# GPIO_Raspberry_b.net
KiCad netlist of a schematic drawn in Altium Designer
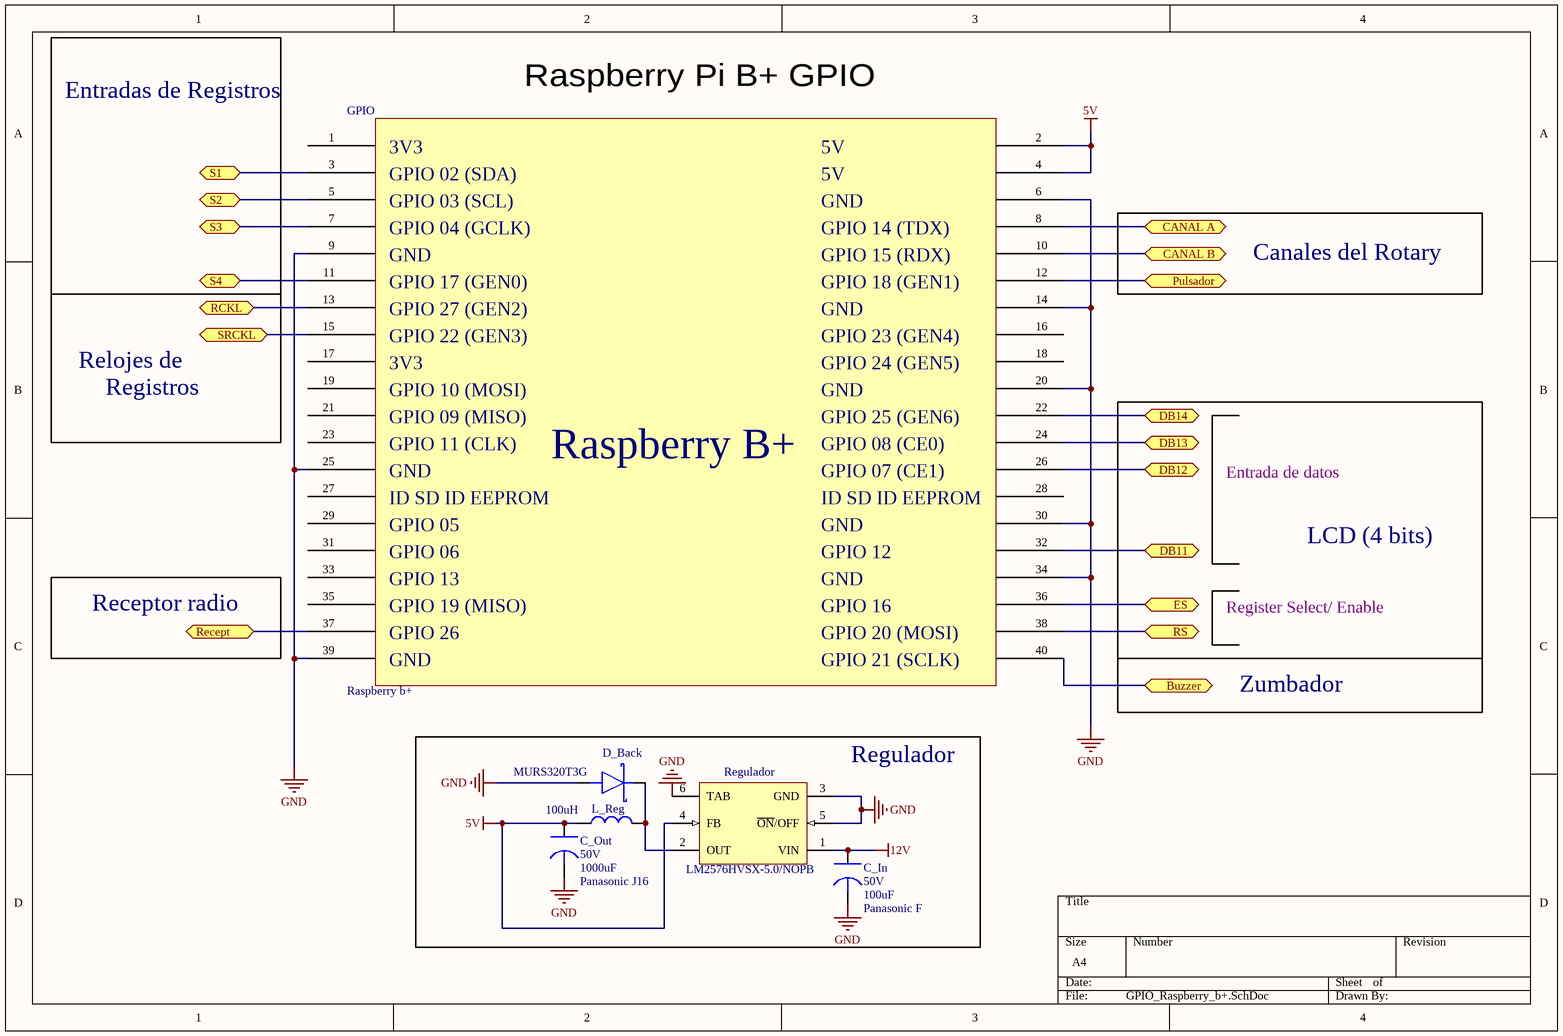
[diagram p0: GPIO_Raspberry_b+.SchDoc]

(export (version "E")
  (design (tool "Eeschema 10.0.6"))
  (components
    (comp (ref "C_In")
      (value "100uF")
      (footprint "Panasonic F Size")
      (description "Condensador Electrolítico SMD")
      (fields
        (field (name "PART NUMBER") "EMV-500ADA101MJA0G")
        (field (name "TOLERANCE") "20%")
        (field (name "VOLTAGE RATING") "50V")
        (field (name "PCB DECAL") "Panasonic F")
        (field (name "AUTHOR") "Jaime Jiménez Ortega")
      )
      (libsource (lib "Libreria_Organo") (part "Panasonic 100uF"))
    )
    (comp (ref "C_Out")
      (value "1000uF")
      (footprint "Panasonic J16 Size")
      (description "Condensador Electrolítico SMD")
      (fields
        (field (name "PART NUMBER") "EMV-500ADA101MJA0G")
        (field (name "TOLERANCE") "20%")
        (field (name "VOLTAGE RATING") "50V")
        (field (name "PCB DECAL") "Panasonic J16")
        (field (name "AUTHOR") "Jaime Jiménez Ortega")
      )
      (libsource (lib "Libreria_Organo") (part "Panasonic 1000uF"))
    )
    (comp (ref "D_Back")
      (value "MURS320T3G")
      (footprint "DO-214AB")
      (description "Surface Mount Schottky-Rectifiers")
      (fields (field (name "AUTHOR") "Jaime Jiménez Ortega"))
      (libsource (lib "Libreria_Organo") (part "MURS320T3G"))
    )
    (comp (ref "GPIO")
      (value "Raspberry b+")
      (footprint "Raspberry")
      (libsource (lib "Libreria_Organo") (part "Raspberry b+"))
    )
    (comp (ref "L_Reg")
      (value "100uH")
      (footprint "DO-5040H 15uH-1400uH")
      (description "Inductor")
      (fields
        (field (name "PART NUMBER") "DO5040H-104ML_")
        (field (name "Comment") "DO-5040H-104ML_")
        (field (name "AUTHOR") "Jaime Jiménez Ortega")
      )
      (libsource (lib "Libreria_Organo") (part "Inductor"))
    )
    (comp (ref "Regulador")
      (value "LM2576HVSX-5.0/NOPB")
      (footprint "TS5B_N_")
      (description "SIMPLE SWITCHER® 3A Step-Down Voltage Regulator, 5-pin TO-263, Pb-Free")
      (fields
        (field (name "MANUFACTURER") "National Semiconductor")
        (field (name "PUBLISHER") "Altium Limited")
      )
      (libsource (lib "Libreria_Organo") (part "LM2576HVSX-5.0/NOPB"))
    )
  )
  (nets
    (net (code "1") (name "/Buzzer") (class "Default")
      (node (ref "GPIO") (pin "40") (pinfunction "40_40") (pintype "passive"))
    )
    (net (code "2") (name "/CANAL A") (class "Default")
      (node (ref "GPIO") (pin "8") (pinfunction "8_8") (pintype "passive"))
    )
    (net (code "3") (name "/CANAL B") (class "Default")
      (node (ref "GPIO") (pin "10") (pinfunction "10_10") (pintype "passive"))
    )
    (net (code "4") (name "/DB11") (class "Default")
      (node (ref "GPIO") (pin "32") (pinfunction "32_32") (pintype "passive"))
    )
    (net (code "5") (name "/DB12") (class "Default")
      (node (ref "GPIO") (pin "26") (pinfunction "26_26") (pintype "passive"))
    )
    (net (code "6") (name "/DB13") (class "Default")
      (node (ref "GPIO") (pin "24") (pinfunction "24_24") (pintype "passive"))
    )
    (net (code "7") (name "/DB14") (class "Default")
      (node (ref "GPIO") (pin "22") (pinfunction "22_22") (pintype "passive"))
    )
    (net (code "8") (name "/ES") (class "Default")
      (node (ref "GPIO") (pin "36") (pinfunction "36_36") (pintype "passive"))
    )
    (net (code "9") (name "/Pulsador") (class "Default")
      (node (ref "GPIO") (pin "12") (pinfunction "12_12") (pintype "passive"))
    )
    (net (code "10") (name "/RCKL") (class "Default")
      (node (ref "GPIO") (pin "13") (pinfunction "13_13") (pintype "passive"))
    )
    (net (code "11") (name "/RS") (class "Default")
      (node (ref "GPIO") (pin "38") (pinfunction "38_38") (pintype "passive"))
    )
    (net (code "12") (name "/Recept") (class "Default")
      (node (ref "GPIO") (pin "37") (pinfunction "37_37") (pintype "passive"))
    )
    (net (code "13") (name "/S1") (class "Default")
      (node (ref "GPIO") (pin "3") (pinfunction "3_3") (pintype "passive"))
    )
    (net (code "14") (name "/S2") (class "Default")
      (node (ref "GPIO") (pin "5") (pinfunction "5_5") (pintype "passive"))
    )
    (net (code "15") (name "/S3") (class "Default")
      (node (ref "GPIO") (pin "7") (pinfunction "7_7") (pintype "passive"))
    )
    (net (code "16") (name "/S4") (class "Default")
      (node (ref "GPIO") (pin "11") (pinfunction "11_11") (pintype "passive"))
    )
    (net (code "17") (name "/SRCKL") (class "Default")
      (node (ref "GPIO") (pin "15") (pinfunction "15_15") (pintype "passive"))
    )
    (net (code "18") (name "5V") (class "Default")
      (node (ref "C_Out") (pin "1") (pintype "power_in"))
      (node (ref "GPIO") (pin "2") (pinfunction "2_2") (pintype "passive"))
      (node (ref "GPIO") (pin "4") (pinfunction "4_4") (pintype "passive"))
      (node (ref "L_Reg") (pin "1") (pintype "passive"))
      (node (ref "Regulador") (pin "4") (pinfunction "FB_4") (pintype "input"))
    )
    (net (code "19") (name "12V") (class "Default")
      (node (ref "C_In") (pin "1") (pintype "power_in"))
      (node (ref "Regulador") (pin "1") (pinfunction "VIN_1") (pintype "power_in"))
    )
    (net (code "20") (name "GND") (class "Default")
      (node (ref "C_In") (pin "2") (pintype "power_in"))
      (node (ref "C_Out") (pin "2") (pintype "power_in"))
      (node (ref "D_Back") (pin "A") (pinfunction "A_A") (pintype "passive"))
      (node (ref "GPIO") (pin "14") (pinfunction "14_14") (pintype "passive"))
      (node (ref "GPIO") (pin "20") (pinfunction "20_20") (pintype "passive"))
      (node (ref "GPIO") (pin "25") (pinfunction "25_25") (pintype "passive"))
      (node (ref "GPIO") (pin "30") (pinfunction "30_30") (pintype "passive"))
      (node (ref "GPIO") (pin "34") (pinfunction "34_34") (pintype "passive"))
      (node (ref "GPIO") (pin "39") (pinfunction "39_39") (pintype "passive"))
      (node (ref "GPIO") (pin "6") (pinfunction "6_6") (pintype "passive"))
      (node (ref "GPIO") (pin "9") (pinfunction "9_9") (pintype "passive"))
      (node (ref "Regulador") (pin "3") (pinfunction "GND_3") (pintype "power_in"))
      (node (ref "Regulador") (pin "5") (pinfunction "~{ON}/OFF_5") (pintype "input"))
      (node (ref "Regulador") (pin "6") (pinfunction "TAB_6") (pintype "power_in"))
    )
    (net (code "21") (name "Net-(Regulador-OUT)") (class "Default")
      (node (ref "D_Back") (pin "K") (pinfunction "K_K") (pintype "passive"))
      (node (ref "L_Reg") (pin "2") (pintype "passive"))
      (node (ref "Regulador") (pin "2") (pinfunction "OUT_2") (pintype "power_in"))
    )
    (net (code "22") (name "unconnected-(GPIO-Pad1)") (class "Default")
      (node (ref "GPIO") (pin "1") (pinfunction "1_1") (pintype "passive"))
    )
    (net (code "23") (name "unconnected-(GPIO-Pad16)") (class "Default")
      (node (ref "GPIO") (pin "16") (pinfunction "16_16") (pintype "passive"))
    )
    (net (code "24") (name "unconnected-(GPIO-Pad17)") (class "Default")
      (node (ref "GPIO") (pin "17") (pinfunction "17_17") (pintype "passive"))
    )
    (net (code "25") (name "unconnected-(GPIO-Pad18)") (class "Default")
      (node (ref "GPIO") (pin "18") (pinfunction "18_18") (pintype "passive"))
    )
    (net (code "26") (name "unconnected-(GPIO-Pad19)") (class "Default")
      (node (ref "GPIO") (pin "19") (pinfunction "19_19") (pintype "passive"))
    )
    (net (code "27") (name "unconnected-(GPIO-Pad21)") (class "Default")
      (node (ref "GPIO") (pin "21") (pinfunction "21_21") (pintype "passive"))
    )
    (net (code "28") (name "unconnected-(GPIO-Pad23)") (class "Default")
      (node (ref "GPIO") (pin "23") (pinfunction "23_23") (pintype "passive"))
    )
    (net (code "29") (name "unconnected-(GPIO-Pad27)") (class "Default")
      (node (ref "GPIO") (pin "27") (pinfunction "27_27") (pintype "passive"))
    )
    (net (code "30") (name "unconnected-(GPIO-Pad28)") (class "Default")
      (node (ref "GPIO") (pin "28") (pinfunction "28_28") (pintype "passive"))
    )
    (net (code "31") (name "unconnected-(GPIO-Pad29)") (class "Default")
      (node (ref "GPIO") (pin "29") (pinfunction "29_29") (pintype "passive"))
    )
    (net (code "32") (name "unconnected-(GPIO-Pad31)") (class "Default")
      (node (ref "GPIO") (pin "31") (pinfunction "31_31") (pintype "passive"))
    )
    (net (code "33") (name "unconnected-(GPIO-Pad33)") (class "Default")
      (node (ref "GPIO") (pin "33") (pinfunction "33_33") (pintype "passive"))
    )
    (net (code "34") (name "unconnected-(GPIO-Pad35)") (class "Default")
      (node (ref "GPIO") (pin "35") (pinfunction "35_35") (pintype "passive"))
    )
  )
)
